# SCH_magic-light-thing_2026-02-07.net
KiCad netlist of a schematic drawn in EasyEDA
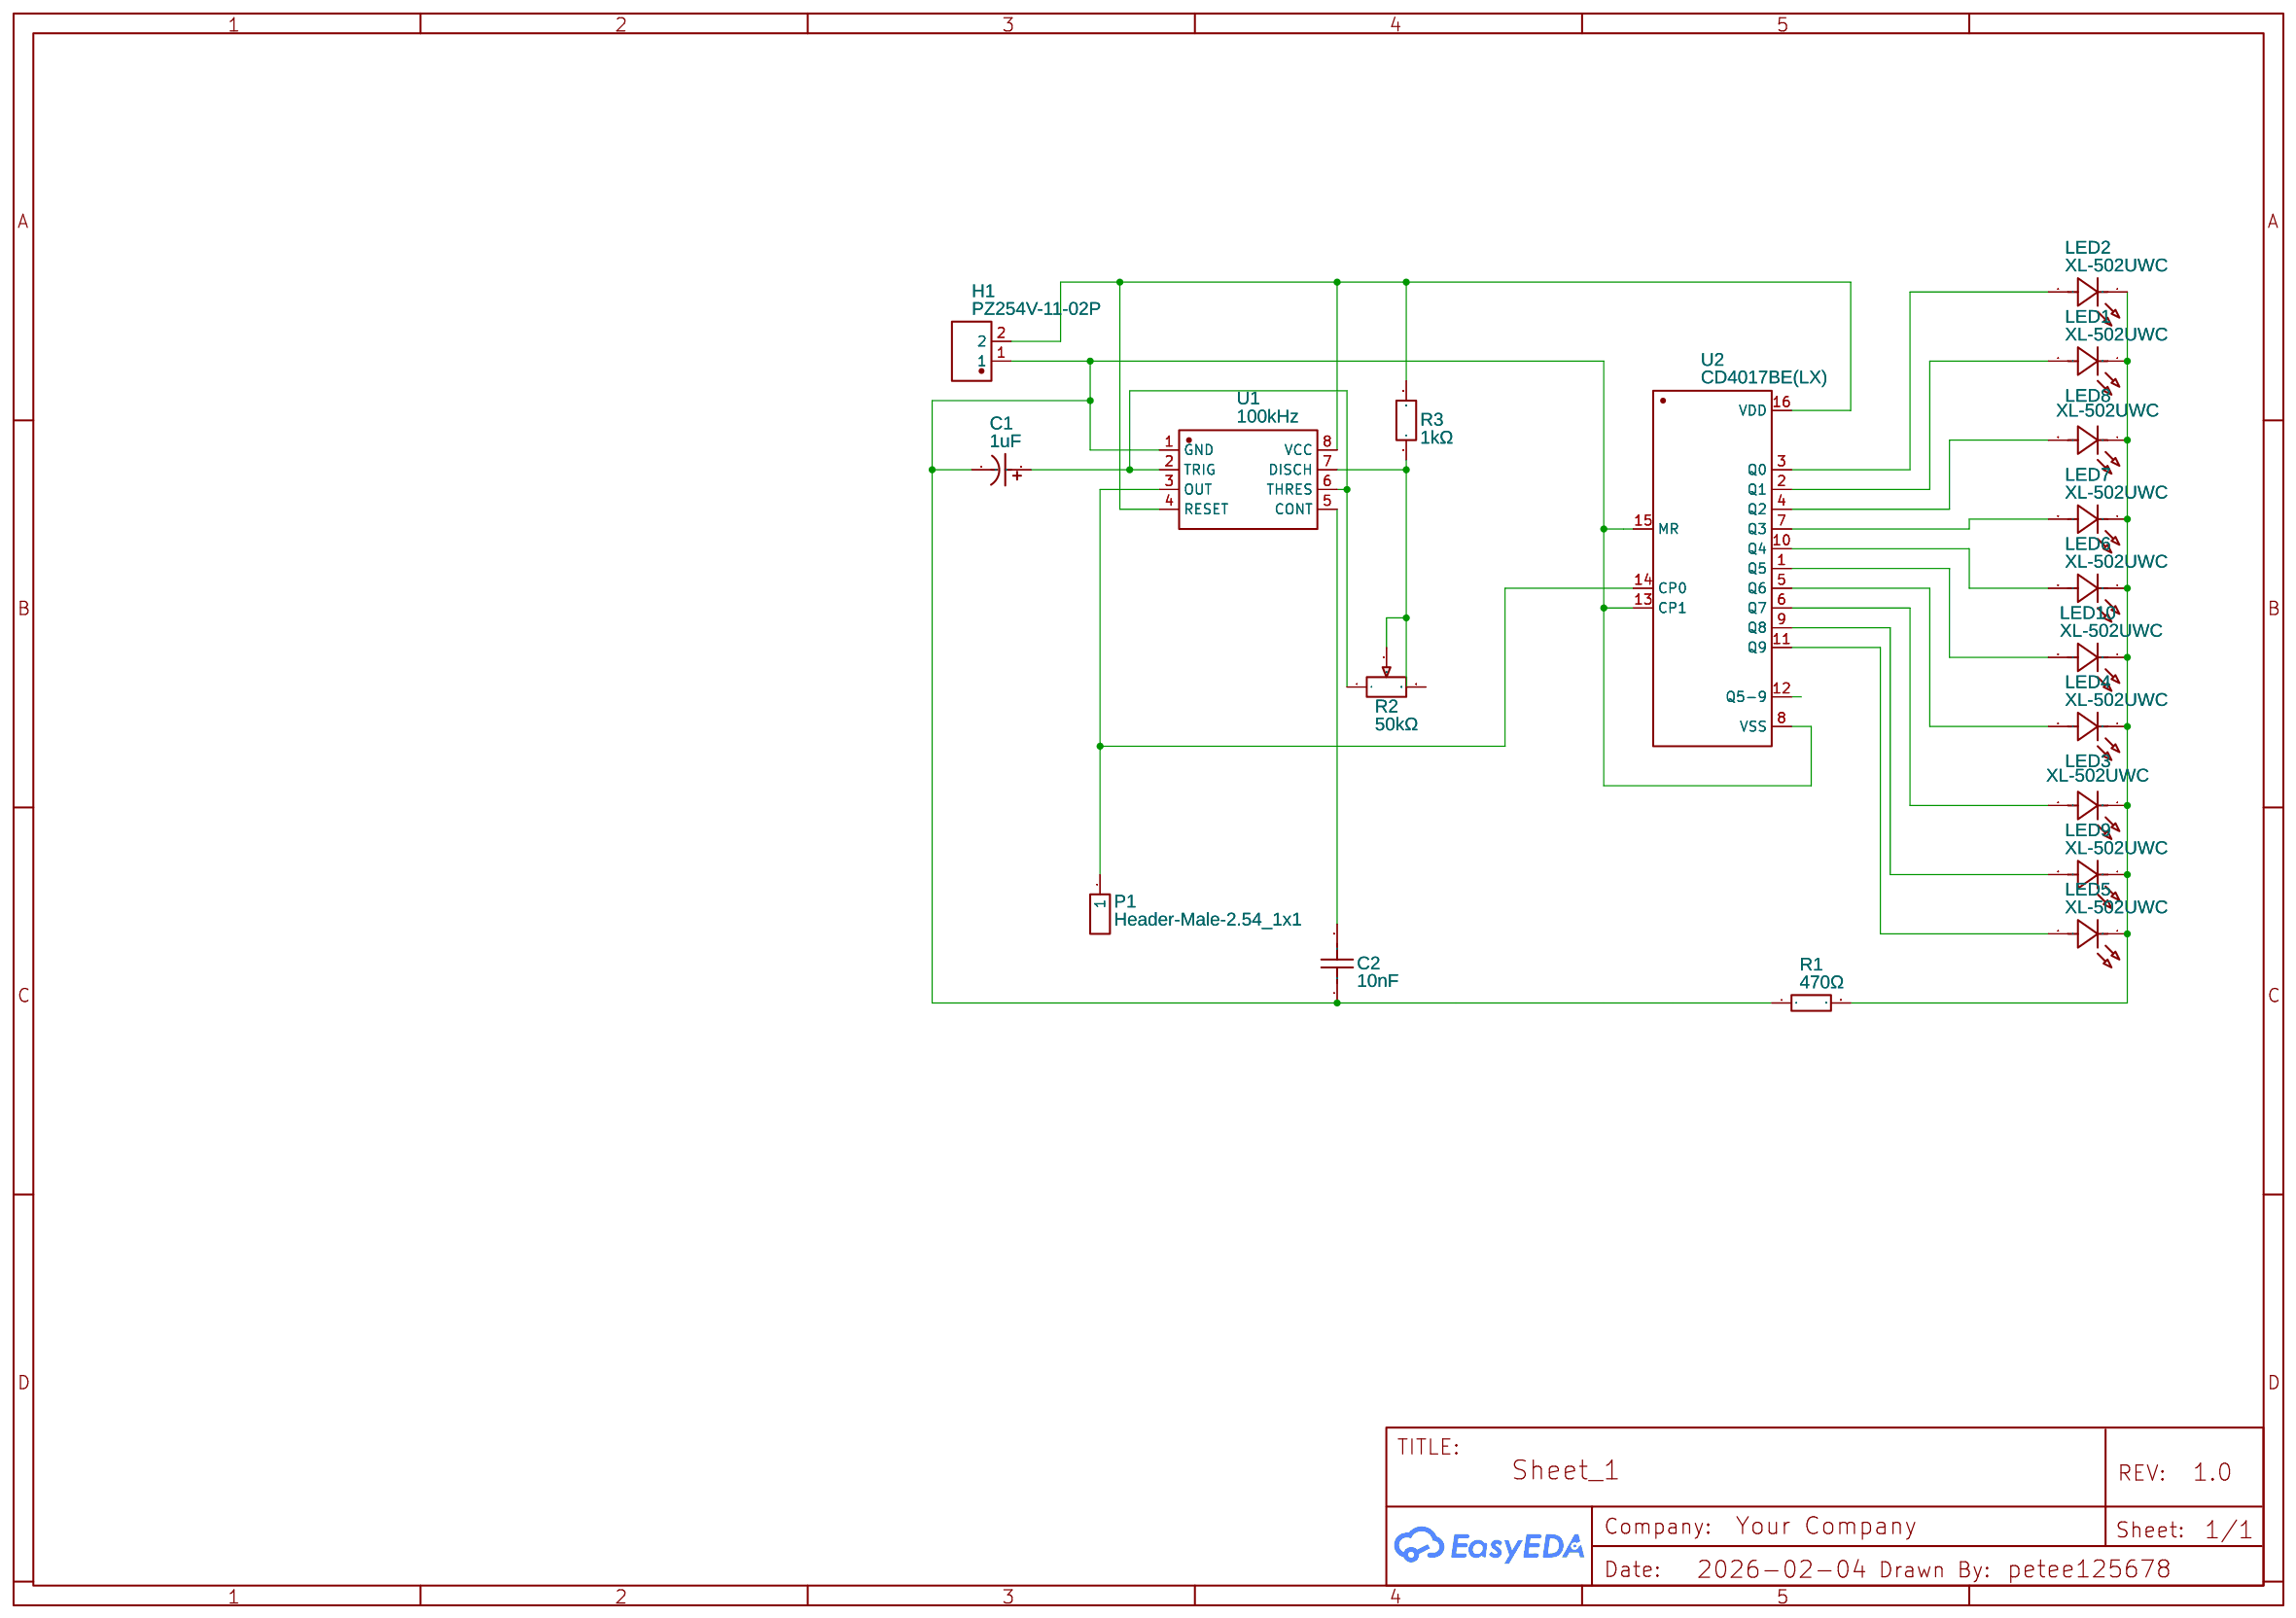
[diagram p0: schematic sheet]

(export (version "E")
  (design (tool "Eeschema 10.0.6"))
  (components
    (comp (ref "C1")
      (value "1uF")
      (fields (field (name "Manufacturer Part") "KF010M050C110A") (field (name "Manufacturer") "CapXon(丰宾)"))
      (libsource (lib "") (part "KF010M050C110A"))
    )
    (comp (ref "C2")
      (value "10nF")
      (fields (field (name "Manufacturer Part") "N09F1B103MN0B0S0N0") (field (name "Manufacturer") "STE(松田)"))
      (libsource (lib "") (part "N09F1B103MN0B0S0N0"))
    )
    (comp (ref "H1")
      (value "PZ254V-11-02P")
      (fields (field (name "Manufacturer") "XFCN(兴飞)"))
      (libsource (lib "") (part "PZ254V-11-02P"))
    )
    (comp (ref "LED1")
      (value "XL-502UWC")
      (fields (field (name "Manufacturer") "XINGLIGHT(成兴光)"))
      (libsource (lib "") (part "XL-502UWC"))
    )
    (comp (ref "LED2")
      (value "XL-502UWC")
      (fields (field (name "Manufacturer") "XINGLIGHT(成兴光)"))
      (libsource (lib "") (part "XL-502UWC"))
    )
    (comp (ref "LED3")
      (value "XL-502UWC")
      (fields (field (name "Manufacturer") "XINGLIGHT(成兴光)"))
      (libsource (lib "") (part "XL-502UWC"))
    )
    (comp (ref "LED4")
      (value "XL-502UWC")
      (fields (field (name "Manufacturer") "XINGLIGHT(成兴光)"))
      (libsource (lib "") (part "XL-502UWC"))
    )
    (comp (ref "LED5")
      (value "XL-502UWC")
      (fields (field (name "Manufacturer") "XINGLIGHT(成兴光)"))
      (libsource (lib "") (part "XL-502UWC"))
    )
    (comp (ref "LED6")
      (value "XL-502UWC")
      (fields (field (name "Manufacturer") "XINGLIGHT(成兴光)"))
      (libsource (lib "") (part "XL-502UWC"))
    )
    (comp (ref "LED7")
      (value "XL-502UWC")
      (fields (field (name "Manufacturer") "XINGLIGHT(成兴光)"))
      (libsource (lib "") (part "XL-502UWC"))
    )
    (comp (ref "LED8")
      (value "XL-502UWC")
      (fields (field (name "Manufacturer") "XINGLIGHT(成兴光)"))
      (libsource (lib "") (part "XL-502UWC"))
    )
    (comp (ref "LED9")
      (value "XL-502UWC")
      (fields (field (name "Manufacturer") "XINGLIGHT(成兴光)"))
      (libsource (lib "") (part "XL-502UWC"))
    )
    (comp (ref "LED10")
      (value "XL-502UWC")
      (fields (field (name "Manufacturer") "XINGLIGHT(成兴光)"))
      (libsource (lib "") (part "XL-502UWC"))
    )
    (comp (ref "P1")
      (value "Header-Male-2.54_1x1")
      (fields (field (name "Manufacturer Part") "2.54-1*1P针") (field (name "Manufacturer") "BOOMELE(博穆精密)"))
      (libsource (lib "") (part "Header-Male-2.54_1x1"))
    )
    (comp (ref "R1")
      (value "470Ω")
      (fields
        (field (name "Manufacturer Part") "MFR0W4F4700A50")
        (field (name "Manufacturer") "UNI-ROYAL(厚声)")
      )
      (libsource (lib "") (part "MFR0W4F4700A50"))
    )
    (comp (ref "R2")
      (value "50kΩ")
      (fields (field (name "Manufacturer Part") "3296X-1-503") (field (name "Manufacturer") "BOCHEN(博晨)"))
      (libsource (lib "") (part "3296X-1-503_C118912"))
    )
    (comp (ref "R3")
      (value "1kΩ")
      (fields (field (name "Manufacturer Part") "MF1/4W-1KΩ±1%T52") (field (name "Manufacturer") "华星机电"))
      (libsource (lib "") (part "MF1/4W-1KΩ±1%T52"))
    )
    (comp (ref "U1")
      (value "100kHz")
      (fields (field (name "Manufacturer Part") "NE555P") (field (name "Manufacturer") "TI(德州仪器)"))
      (libsource (lib "") (part "NE555P"))
    )
    (comp (ref "U2")
      (value "CD4017BE(LX)")
      (fields (field (name "Manufacturer") "LX(灵星芯微)"))
      (libsource (lib "") (part "CD4017BE(LX)"))
    )
  )
  (nets
    (net (code "1") (name "Net-(LED1-A)") (class "Default")
      (node (ref "LED1") (pin "2") (pinfunction "A_2") (pintype "unspecified"))
      (node (ref "U2") (pin "2") (pinfunction "Q1_2") (pintype "unspecified"))
    )
    (net (code "2") (name "Net-(LED1-K)") (class "Default")
      (node (ref "LED1") (pin "1") (pinfunction "K_1") (pintype "unspecified"))
      (node (ref "LED10") (pin "1") (pinfunction "K_1") (pintype "unspecified"))
      (node (ref "LED2") (pin "1") (pinfunction "K_1") (pintype "unspecified"))
      (node (ref "LED3") (pin "1") (pinfunction "K_1") (pintype "unspecified"))
      (node (ref "LED4") (pin "1") (pinfunction "K_1") (pintype "unspecified"))
      (node (ref "LED5") (pin "1") (pinfunction "K_1") (pintype "unspecified"))
      (node (ref "LED6") (pin "1") (pinfunction "K_1") (pintype "unspecified"))
      (node (ref "LED7") (pin "1") (pinfunction "K_1") (pintype "unspecified"))
      (node (ref "LED8") (pin "1") (pinfunction "K_1") (pintype "unspecified"))
      (node (ref "LED9") (pin "1") (pinfunction "K_1") (pintype "unspecified"))
      (node (ref "R1") (pin "2") (pinfunction "2_2") (pintype "input"))
    )
    (net (code "3") (name "Net-(LED2-A)") (class "Default")
      (node (ref "LED2") (pin "2") (pinfunction "A_2") (pintype "unspecified"))
      (node (ref "U2") (pin "3") (pinfunction "Q0_3") (pintype "unspecified"))
    )
    (net (code "4") (name "Net-(LED3-A)") (class "Default")
      (node (ref "LED3") (pin "2") (pinfunction "A_2") (pintype "unspecified"))
      (node (ref "U2") (pin "6") (pinfunction "Q7_6") (pintype "unspecified"))
    )
    (net (code "5") (name "Net-(LED4-A)") (class "Default")
      (node (ref "LED4") (pin "2") (pinfunction "A_2") (pintype "unspecified"))
      (node (ref "U2") (pin "5") (pinfunction "Q6_5") (pintype "unspecified"))
    )
    (net (code "6") (name "Net-(LED5-A)") (class "Default")
      (node (ref "LED5") (pin "2") (pinfunction "A_2") (pintype "unspecified"))
      (node (ref "U2") (pin "11") (pinfunction "Q9_11") (pintype "unspecified"))
    )
    (net (code "7") (name "Net-(LED6-A)") (class "Default")
      (node (ref "LED6") (pin "2") (pinfunction "A_2") (pintype "unspecified"))
      (node (ref "U2") (pin "10") (pinfunction "Q4_10") (pintype "unspecified"))
    )
    (net (code "8") (name "Net-(LED7-A)") (class "Default")
      (node (ref "LED7") (pin "2") (pinfunction "A_2") (pintype "unspecified"))
      (node (ref "U2") (pin "7") (pinfunction "Q3_7") (pintype "unspecified"))
    )
    (net (code "9") (name "Net-(LED8-A)") (class "Default")
      (node (ref "LED8") (pin "2") (pinfunction "A_2") (pintype "unspecified"))
      (node (ref "U2") (pin "4") (pinfunction "Q2_4") (pintype "unspecified"))
    )
    (net (code "10") (name "Net-(LED9-A)") (class "Default")
      (node (ref "LED9") (pin "2") (pinfunction "A_2") (pintype "unspecified"))
      (node (ref "U2") (pin "9") (pinfunction "Q8_9") (pintype "unspecified"))
    )
    (net (code "11") (name "Net-(LED10-A)") (class "Default")
      (node (ref "LED10") (pin "2") (pinfunction "A_2") (pintype "unspecified"))
      (node (ref "U2") (pin "1") (pinfunction "Q5_1") (pintype "unspecified"))
    )
    (net (code "12") (name "Net-(U1-CONT)") (class "Default")
      (node (ref "C2") (pin "2") (pinfunction "2_2") (pintype "unspecified"))
      (node (ref "U1") (pin "5") (pinfunction "CONT_5") (pintype "unspecified"))
    )
    (net (code "13") (name "Net-(U1-DISCH)") (class "Default")
      (node (ref "R2") (pin "2") (pinfunction "2_2") (pintype "input"))
      (node (ref "R2") (pin "3") (pinfunction "3_3") (pintype "input"))
      (node (ref "R3") (pin "1") (pinfunction "1_1") (pintype "unspecified"))
      (node (ref "U1") (pin "7") (pinfunction "DISCH_7") (pintype "unspecified"))
    )
    (net (code "14") (name "Net-(U1-GND)") (class "Default")
      (node (ref "C1") (pin "2") (pinfunction "2_2") (pintype "input"))
      (node (ref "C2") (pin "1") (pinfunction "1_1") (pintype "unspecified"))
      (node (ref "H1") (pin "1") (pinfunction "1_1") (pintype "unspecified"))
      (node (ref "R1") (pin "1") (pinfunction "1_1") (pintype "input"))
      (node (ref "U1") (pin "1") (pinfunction "GND_1") (pintype "unspecified"))
      (node (ref "U2") (pin "13") (pinfunction "CP1_13") (pintype "unspecified"))
      (node (ref "U2") (pin "15") (pinfunction "MR_15") (pintype "unspecified"))
      (node (ref "U2") (pin "8") (pinfunction "VSS_8") (pintype "unspecified"))
    )
    (net (code "15") (name "Net-(U1-OUT)") (class "Default")
      (node (ref "P1") (pin "1") (pinfunction "1_1") (pintype "input"))
      (node (ref "U1") (pin "3") (pinfunction "OUT_3") (pintype "unspecified"))
      (node (ref "U2") (pin "14") (pinfunction "CP0_14") (pintype "unspecified"))
    )
    (net (code "16") (name "Net-(U1-RESET)") (class "Default")
      (node (ref "H1") (pin "2") (pinfunction "2_2") (pintype "unspecified"))
      (node (ref "R3") (pin "2") (pinfunction "2_2") (pintype "unspecified"))
      (node (ref "U1") (pin "4") (pinfunction "RESET_4") (pintype "unspecified"))
      (node (ref "U1") (pin "8") (pinfunction "VCC_8") (pintype "unspecified"))
      (node (ref "U2") (pin "16") (pinfunction "VDD_16") (pintype "unspecified"))
    )
    (net (code "17") (name "Net-(U1-THRES)") (class "Default")
      (node (ref "C1") (pin "1") (pinfunction "1_1") (pintype "input"))
      (node (ref "R2") (pin "1") (pinfunction "1_1") (pintype "input"))
      (node (ref "U1") (pin "2") (pinfunction "TRIG_2") (pintype "unspecified"))
      (node (ref "U1") (pin "6") (pinfunction "THRES_6") (pintype "unspecified"))
    )
    (net (code "18") (name "unconnected-(U2-Q5-9-Pad12)") (class "Default")
      (node (ref "U2") (pin "12") (pinfunction "Q5-9_12") (pintype "unspecified"))
    )
  )
)
